# Sheet1.net
KiCad netlist of a schematic drawn in Altium Designer
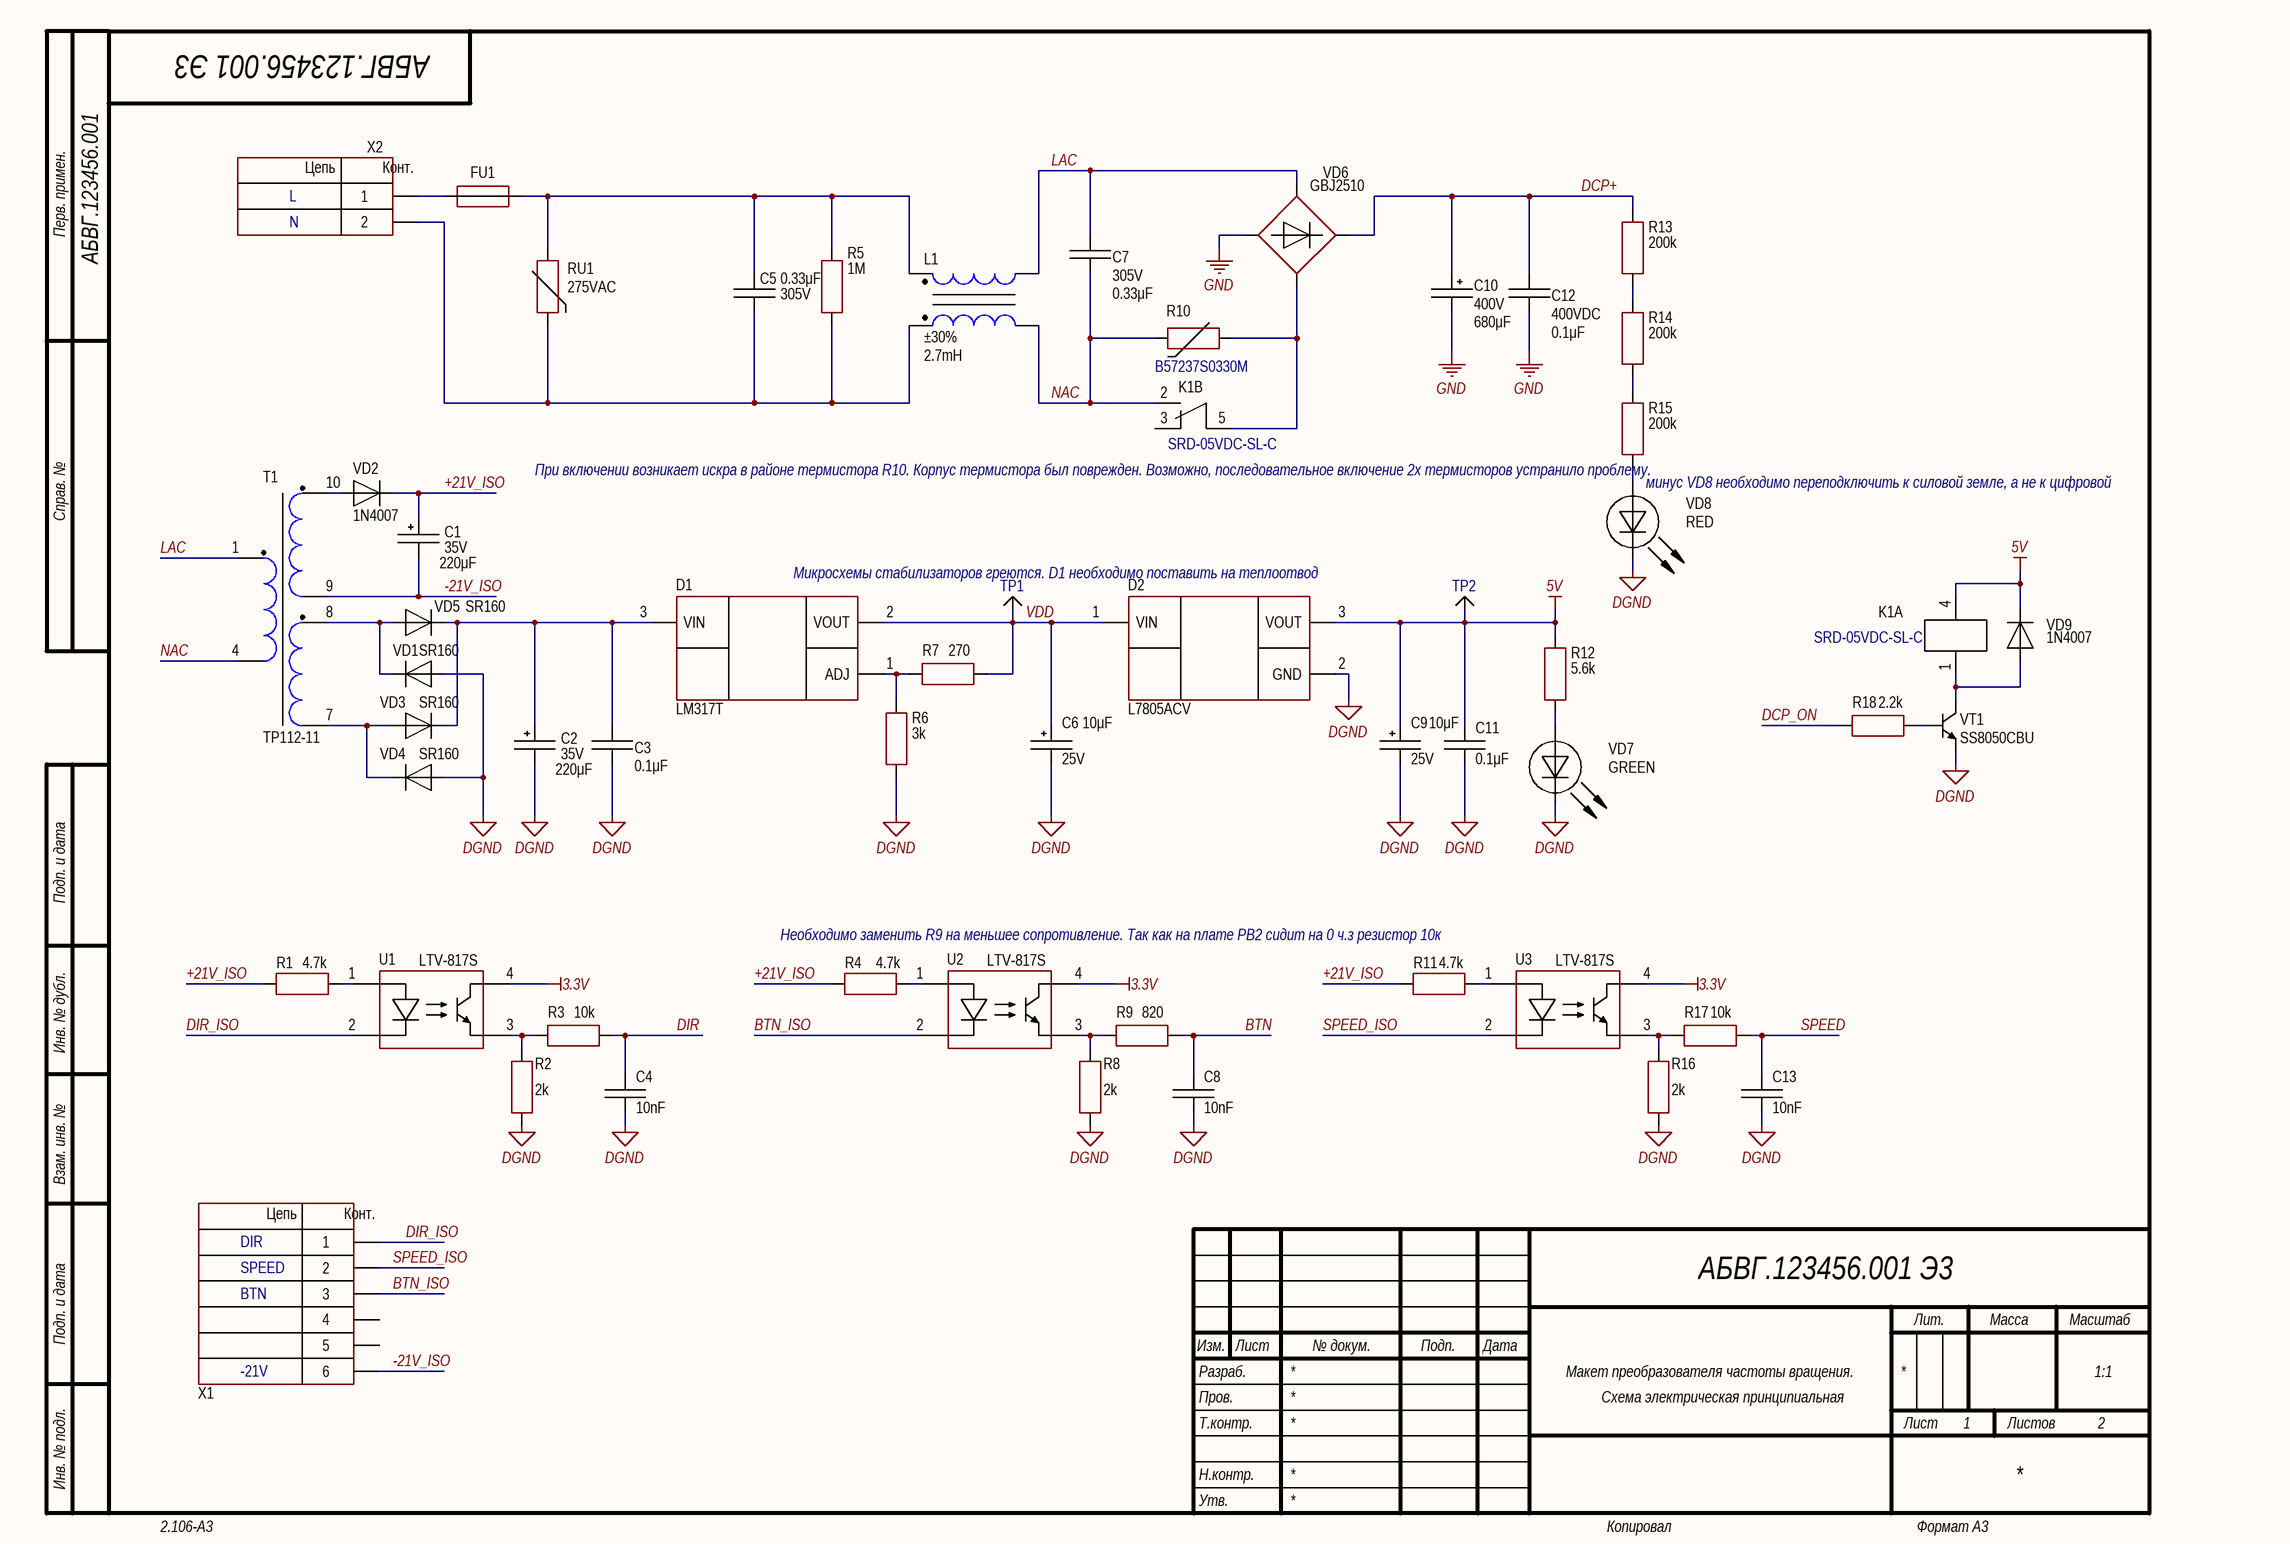
[diagram p0: Sheet1.SchDoc]

(export (version "E")
  (design (tool "Eeschema 10.0.6"))
  (components
    (comp (ref "C1")
      (value "220μF")
      (footprint "CAP: D8C3.5H12")
      (fields
        (field (name "MANUFACTURER") "?")
        (field (name "PARTNUMBER") "9000565901")
        (field (name "VALUEMANUFACTURERPARTNUMBER") "Aluminium capacitor, 220μF, 35V, ±20%, 54mOhm, 8x12x3.5 mm, -40...+105°C")
        (field (name "VOLTAGE") "35V")
      )
      (libsource (lib "capacitor") (part "Aluminium"))
    )
    (comp (ref "C2")
      (value "220μF")
      (footprint "CAP: D8C3.5H12")
      (fields
        (field (name "MANUFACTURER") "?")
        (field (name "PARTNUMBER") "9000565901")
        (field (name "VALUEMANUFACTURERPARTNUMBER") "Aluminium capacitor, 220μF, 35V, ±20%, 54mOhm, 8x12x3.5 mm, -40...+105°C")
        (field (name "VOLTAGE") "35V")
      )
      (libsource (lib "capacitor") (part "Aluminium"))
    )
    (comp (ref "C3")
      (value "0.1μF")
      (footprint "CAP: 1206")
      (fields
        (field (name "PARTNUMBER") "Ceramic capacitor, 0.1μF,   50V")
        (field (name "VALUEMANUFACTURERPARTNUMBER") "Ceramic capacitor, 0.1μF, X7R, ±10%, 50V, 1206, -55...+125°C")
        (field (name "TOLERANCE") "±10%")
      )
      (libsource (lib "capacitor") (part "Ceramic_1206"))
    )
    (comp (ref "C4")
      (value "10nF")
      (footprint "CAP: 1206")
      (fields
        (field (name "PARTNUMBER") "Ceramic capacitor, 10nF,   50V")
        (field (name "VALUEMANUFACTURERPARTNUMBER") "Ceramic capacitor, 10nF, X7R, ±10%, 50V, 1206, -55...+125°C")
        (field (name "TOLERANCE") "±10%")
      )
      (libsource (lib "capacitor") (part "Ceramic_1206"))
    )
    (comp (ref "C5")
      (value "0.33μF")
      (footprint "CAP: B32922")
      (fields
        (field (name "MANUFACTURER") "Epcos")
        (field (name "PARTNUMBER") "B32922-C3334-K")
        (field (name "VALUEMANUFACTURERPARTNUMBER") "Film capacitor X2, 0.33μF, 305V, ±10%, ?, 18x14x8, -40...+110°C")
        (field (name "VOLTAGE") "305V")
      )
      (libsource (lib "capacitor") (part "Film"))
    )
    (comp (ref "C6")
      (value "10μF")
      (footprint "CAP: D5C2H11")
      (fields
        (field (name "MANUFACTURER") "?")
        (field (name "PARTNUMBER") "9000565842")
        (field (name "VALUEMANUFACTURERPARTNUMBER") "Aluminium capacitor, 10μF, 25V, ±20%, 54mOhm, ?, -40...+105°C")
        (field (name "VOLTAGE") "25V")
      )
      (libsource (lib "capacitor") (part "Aluminium"))
    )
    (comp (ref "C7")
      (value "0.33μF")
      (footprint "CAP: B32922")
      (fields
        (field (name "MANUFACTURER") "Epcos")
        (field (name "PARTNUMBER") "B32922-C3334-K")
        (field (name "VALUEMANUFACTURERPARTNUMBER") "Film capacitor X2, 0.33μF, 305V, ±10%, ?, 18x14x8, -40...+110°C")
        (field (name "VOLTAGE") "305V")
      )
      (libsource (lib "capacitor") (part "Film"))
    )
    (comp (ref "C8")
      (value "10nF")
      (footprint "CAP: 1206")
      (fields
        (field (name "PARTNUMBER") "Ceramic capacitor, 10nF,   50V")
        (field (name "VALUEMANUFACTURERPARTNUMBER") "Ceramic capacitor, 10nF, X7R, ±10%, 50V, 1206, -55...+125°C")
        (field (name "TOLERANCE") "±10%")
      )
      (libsource (lib "capacitor") (part "Ceramic_1206"))
    )
    (comp (ref "C9")
      (value "10μF")
      (footprint "CAP: D5C2H11")
      (fields
        (field (name "MANUFACTURER") "?")
        (field (name "PARTNUMBER") "9000565842")
        (field (name "VALUEMANUFACTURERPARTNUMBER") "Aluminium capacitor, 10μF, 25V, ±20%, 54mOhm, ?, -40...+105°C")
        (field (name "VOLTAGE") "25V")
      )
      (libsource (lib "capacitor") (part "Aluminium"))
    )
    (comp (ref "C10")
      (value "680μF")
      (footprint "CAP: D30C10H37")
      (fields
        (field (name "MANUFACTURER") "JB Capacitors")
        (field (name "PARTNUMBER") "JNE2G681M10003000600")
        (field (name "VALUEMANUFACTURERPARTNUMBER") "Aluminium capacitor, 680μF, 400V, ±20%, ?, 30x10x60 mm, -25...+105°C")
        (field (name "VOLTAGE") "400V")
      )
      (libsource (lib "capacitor") (part "Aluminium"))
    )
    (comp (ref "C11")
      (value "0.1μF")
      (footprint "CAP: 1206")
      (fields
        (field (name "PARTNUMBER") "Ceramic capacitor, 0.1μF,   50V")
        (field (name "VALUEMANUFACTURERPARTNUMBER") "Ceramic capacitor, 0.1μF, X7R, ±10%, 50V, 1206, -55...+125°C")
        (field (name "TOLERANCE") "±10%")
      )
      (libsource (lib "capacitor") (part "Ceramic_1206"))
    )
    (comp (ref "C12")
      (value "0.1μF")
      (footprint "CAP: B32673")
      (fields
        (field (name "MANUFACTURER") "Epcos")
        (field (name "PARTNUMBER") "B32683A4104J000")
        (field (name "VALUEMANUFACTURERPARTNUMBER") "Film capacitor, 0.1μF, 400VDC, ±10%, ?, 26.5x16.5x8.5 mm, -55...+100°C")
        (field (name "VOLTAGE") "400VDC")
      )
      (libsource (lib "capacitor") (part "Film"))
    )
    (comp (ref "C13")
      (value "10nF")
      (footprint "CAP: 1206")
      (fields
        (field (name "PARTNUMBER") "Ceramic capacitor, 10nF,   50V")
        (field (name "VALUEMANUFACTURERPARTNUMBER") "Ceramic capacitor, 10nF, X7R, ±10%, 50V, 1206, -55...+125°C")
        (field (name "TOLERANCE") "±10%")
      )
      (libsource (lib "capacitor") (part "Ceramic_1206"))
    )
    (comp (ref "D1")
      (value "~")
      (footprint "TO-220F")
      (description "Adjustable voltage regulator")
      (fields
        (field (name "MANUFACTURER") "STMicroelectronics")
        (field (name "VALUEMANUFACTURERPARTNUMBER") "Adjustable voltage regulator, , , , 0...125°C, TO-220SG")
        (field (name "PARTNUMBER") "LM317T")
      )
      (libsource (lib "ic-power-supply") (part "LM317"))
    )
    (comp (ref "D2")
      (value "~")
      (footprint "TO-220F")
      (description "Linear voltage regulator")
      (fields
        (field (name "MANUFACTURER") "STMicroelectronics")
        (field (name "VALUEMANUFACTURERPARTNUMBER") "Linear voltage regulator, , , , *, *")
        (field (name "PARTNUMBER") "L7805ACV")
      )
      (libsource (lib "ic-power-supply") (part "78XX"))
    )
    (comp (ref "FU1")
      (value "~")
      (footprint "FUSE: FH-101")
      (fields
        (field (name "MANUFACTURER") "Dragon City Industries")
        (field (name "PARTNUMBER") "FH-101")
        (field (name "VALUEMANUFACTURERPARTNUMBER") "*,  FH-101, *")
      )
      (libsource (lib "resistor") (part "FUSE"))
    )
    (comp (ref "K1")
      (value "Relay, Non Latching, SPDT , 10A , (250VAC , 110VDC)")
      (footprint "SRD-05VDC-SL-C")
      (fields
        (field (name "MANUFACTURER") "Ningbo Songle Relay")
        (field (name "PARTNUMBER") "SRD-05VDC-SL-C")
      )
      (libsource (lib "") (part "SRD-05VDC-SL-C_1"))
    )
    (comp (ref "L1")
      (value "2.7mH")
      (footprint "IND: B82723A")
      (fields
        (field (name "MANUFACTURER") "TDK (TDK-Lambda)")
        (field (name "PARTNUMBER") "B82723A2402N1")
        (field (name "VALUEMANUFACTURERPARTNUMBER") "Fixed inductor, 2.7mH, ±30%, B82723A, CuNi18Zn20, ")
        (field (name "TOLERANCE") "±30%")
      )
      (libsource (lib "inductor") (part "B82723A"))
    )
    (comp (ref "R1")
      (value "4.7k")
      (footprint "RES: 1206")
      (fields
        (field (name "MANUFACTURER") "Yageo")
        (field (name "PARTNUMBER") "RC1206JR-07100RL")
        (field (name "VALUEMANUFACTURERPARTNUMBER") "Resistor film, 4.7k, ±5%, 1206, 0.25W, -55...+125°C")
      )
      (libsource (lib "") (part "Resistor_1206_2"))
    )
    (comp (ref "R2")
      (value "2k")
      (footprint "RES: 1206")
      (fields
        (field (name "MANUFACTURER") "Yageo")
        (field (name "PARTNUMBER") "RC1206JR-07100RL")
        (field (name "VALUEMANUFACTURERPARTNUMBER") "Resistor film, 2k, ±5%, 1206, 0.25W, -55...+125°C")
      )
      (libsource (lib "resistor") (part "Resistor_1206"))
    )
    (comp (ref "R3")
      (value "10k")
      (footprint "RES: 1206")
      (fields
        (field (name "MANUFACTURER") "Yageo")
        (field (name "PARTNUMBER") "RC1206JR-07100RL")
        (field (name "VALUEMANUFACTURERPARTNUMBER") "Resistor film, 10k, ±5%, 1206, 0.25W, -55...+125°C")
      )
      (libsource (lib "") (part "Resistor_1206_1"))
    )
    (comp (ref "R4")
      (value "4.7k")
      (footprint "RES: 1206")
      (fields
        (field (name "MANUFACTURER") "Yageo")
        (field (name "PARTNUMBER") "RC1206JR-07100RL")
        (field (name "VALUEMANUFACTURERPARTNUMBER") "Resistor film, 4.7k, ±5%, 1206, 0.25W, -55...+125°C")
      )
      (libsource (lib "") (part "Resistor_1206_2"))
    )
    (comp (ref "R5")
      (value "1M")
      (footprint "RES: Axial 15mm")
      (fields (field (name "TOLERANCE") "±5%"))
      (libsource (lib "resistor") (part "Resistor_Axial"))
    )
    (comp (ref "R6")
      (value "3k")
      (footprint "RES: 1206")
      (fields
        (field (name "MANUFACTURER") "Yageo")
        (field (name "PARTNUMBER") "RC1206JR-07100RL")
        (field (name "VALUEMANUFACTURERPARTNUMBER") "Resistor film, 3k, ±5%, 1206, 0.25W, -55...+125°C")
      )
      (libsource (lib "resistor") (part "Resistor_1206"))
    )
    (comp (ref "R7")
      (value "270")
      (footprint "RES: 1206")
      (fields
        (field (name "MANUFACTURER") "Yageo")
        (field (name "PARTNUMBER") "RC1206JR-07100RL")
        (field (name "VALUEMANUFACTURERPARTNUMBER") "Resistor film, 270, ±5%, 1206, 0.25W, -55...+125°C")
      )
      (libsource (lib "") (part "Resistor_1206_2"))
    )
    (comp (ref "R8")
      (value "2k")
      (footprint "RES: 1206")
      (fields
        (field (name "MANUFACTURER") "Yageo")
        (field (name "PARTNUMBER") "RC1206JR-07100RL")
        (field (name "VALUEMANUFACTURERPARTNUMBER") "Resistor film, 2k, ±5%, 1206, 0.25W, -55...+125°C")
      )
      (libsource (lib "resistor") (part "Resistor_1206"))
    )
    (comp (ref "R9")
      (value "820")
      (footprint "RES: 1206")
      (fields
        (field (name "MANUFACTURER") "Yageo")
        (field (name "PARTNUMBER") "RC1206JR-07100RL")
        (field (name "VALUEMANUFACTURERPARTNUMBER") "Resistor film, 820, ±5%, 1206, 0.25W, -55...+125°C")
      )
      (libsource (lib "") (part "Resistor_1206_1"))
    )
    (comp (ref "R10")
      (value "~")
      (footprint "RES: B57237 (NTC)")
      (description "Maximum permissible capacitance 900uF")
      (fields
        (field (name "MANUFACTURER") "Epcos")
        (field (name "PARTNUMBER") "B57237S0330M")
        (field (name "VALUEMANUFACTURERPARTNUMBER") "NTC resistor, 33, ±20%, pitch 7.5mm, 2.5A, -55...+170°C")
      )
      (libsource (lib "resistor") (part "NTC"))
    )
    (comp (ref "R11")
      (value "4.7k")
      (footprint "RES: 1206")
      (fields
        (field (name "MANUFACTURER") "Yageo")
        (field (name "PARTNUMBER") "RC1206JR-07100RL")
        (field (name "VALUEMANUFACTURERPARTNUMBER") "Resistor film, 4.7k, ±5%, 1206, 0.25W, -55...+125°C")
      )
      (libsource (lib "") (part "Resistor_1206_2"))
    )
    (comp (ref "R12")
      (value "5.6k")
      (footprint "RES: 1206")
      (fields
        (field (name "MANUFACTURER") "Yageo")
        (field (name "PARTNUMBER") "RC1206JR-07100RL")
        (field (name "VALUEMANUFACTURERPARTNUMBER") "Resistor film, 5.6k, ±5%, 1206, 0.25W, -55...+125°C")
      )
      (libsource (lib "resistor") (part "Resistor_1206"))
    )
    (comp (ref "R13")
      (value "200k")
      (footprint "RES: 1206")
      (fields
        (field (name "MANUFACTURER") "Yageo")
        (field (name "PARTNUMBER") "RC1206JR-07100RL")
        (field (name "VALUEMANUFACTURERPARTNUMBER") "Resistor film, 200k, ±5%, 1206, 0.25W, -55...+125°C")
      )
      (libsource (lib "resistor") (part "Resistor_1206"))
    )
    (comp (ref "R14")
      (value "200k")
      (footprint "RES: 1206")
      (fields
        (field (name "MANUFACTURER") "Yageo")
        (field (name "PARTNUMBER") "RC1206JR-07100RL")
        (field (name "VALUEMANUFACTURERPARTNUMBER") "Resistor film, 200k, ±5%, 1206, 0.25W, -55...+125°C")
      )
      (libsource (lib "resistor") (part "Resistor_1206"))
    )
    (comp (ref "R15")
      (value "200k")
      (footprint "RES: 1206")
      (fields
        (field (name "MANUFACTURER") "Yageo")
        (field (name "PARTNUMBER") "RC1206JR-07100RL")
        (field (name "VALUEMANUFACTURERPARTNUMBER") "Resistor film, 200k, ±5%, 1206, 0.25W, -55...+125°C")
      )
      (libsource (lib "resistor") (part "Resistor_1206"))
    )
    (comp (ref "R16")
      (value "2k")
      (footprint "RES: 1206")
      (fields
        (field (name "MANUFACTURER") "Yageo")
        (field (name "PARTNUMBER") "RC1206JR-07100RL")
        (field (name "VALUEMANUFACTURERPARTNUMBER") "Resistor film, 2k, ±5%, 1206, 0.25W, -55...+125°C")
      )
      (libsource (lib "resistor") (part "Resistor_1206"))
    )
    (comp (ref "R17")
      (value "10k")
      (footprint "RES: 1206")
      (fields
        (field (name "MANUFACTURER") "Yageo")
        (field (name "PARTNUMBER") "RC1206JR-07100RL")
        (field (name "VALUEMANUFACTURERPARTNUMBER") "Resistor film, 10k, ±5%, 1206, 0.25W, -55...+125°C")
      )
      (libsource (lib "") (part "Resistor_1206_1"))
    )
    (comp (ref "R18")
      (value "2.2k")
      (footprint "RES: 1206")
      (fields
        (field (name "MANUFACTURER") "Yageo")
        (field (name "PARTNUMBER") "RC1206JR-07100RL")
        (field (name "VALUEMANUFACTURERPARTNUMBER") "Resistor film, 2.2k, ±5%, 1206, 0.25W, -55...+125°C")
      )
      (libsource (lib "") (part "Resistor_1206_2"))
    )
    (comp (ref "RU1")
      (value "~")
      (footprint "VARISTOR: B72214")
      (fields
        (field (name "MANUFACTURER") "EPCOS")
        (field (name "PARTNUMBER") "B72214-S 271-K101")
        (field (name "VALUEMANUFACTURERPARTNUMBER") "Varistor, 275VAC, pitch 7mm,  -40…85°C")
        (field (name "MAXVOLTAGE") "275VAC")
      )
      (libsource (lib "resistor") (part "Varistor"))
    )
    (comp (ref "T1")
      (value "~")
      (footprint "TRANS: TP-112")
      (fields
        (field (name "MANUFACTURER") "?")
        (field (name "VALUEMANUFACTURERPARTNUMBER") "Transformer, TP112-11")
        (field (name "PARTNUMBER") "TP112-11")
        (field (name "PACKAGE") "TP112-11")
      )
      (libsource (lib "transformer") (part "TP-112"))
    )
    (comp (ref "TP1")
      (value "Test_Point")
      (footprint "TEST POINT KEYSTONE")
      (libsource (lib "other") (part "Test_Point"))
    )
    (comp (ref "TP2")
      (value "Test_Point")
      (footprint "TEST POINT KEYSTONE")
      (libsource (lib "other") (part "Test_Point"))
    )
    (comp (ref "U1")
      (value "~")
      (footprint "4-SMD")
      (description "Optoisolator")
      (fields
        (field (name "MANUFACTURER") "Lite-On")
        (field (name "VALUEMANUFACTURERPARTNUMBER") "IC optoisolator, 4µs/3µs, 5000Vrms, 35V, -40...+125°C, 4-SMD")
        (field (name "PARTNUMBER") "LTV-817S")
      )
      (libsource (lib "optoisolator") (part "LTV-817"))
    )
    (comp (ref "U2")
      (value "~")
      (footprint "4-SMD")
      (description "Optoisolator")
      (fields
        (field (name "MANUFACTURER") "Lite-On")
        (field (name "VALUEMANUFACTURERPARTNUMBER") "IC optoisolator, 4µs/3µs, 5000Vrms, 35V, -40...+125°C, 4-SMD")
        (field (name "PARTNUMBER") "LTV-817S")
      )
      (libsource (lib "optoisolator") (part "LTV-817"))
    )
    (comp (ref "U3")
      (value "~")
      (footprint "4-SMD")
      (description "Optoisolator")
      (fields
        (field (name "MANUFACTURER") "Lite-On")
        (field (name "VALUEMANUFACTURERPARTNUMBER") "IC optoisolator, 4µs/3µs, 5000Vrms, 35V, -40...+125°C, 4-SMD")
        (field (name "PARTNUMBER") "LTV-817S")
      )
      (libsource (lib "optoisolator") (part "LTV-817"))
    )
    (comp (ref "VD1")
      (value "~")
      (footprint "DIODE: DO41")
      (fields
        (field (name "MANUFACTURER") "China")
        (field (name "VALUEMANUFACTURERPARTNUMBER") "Single diode, 60V, 1A, 700mV, ?, DO-41,  -65…+150°C")
        (field (name "VOLTAGE") "60V")
        (field (name "PARTNUMBER") "SR160")
      )
      (libsource (lib "diode") (part "Diode_single"))
    )
    (comp (ref "VD2")
      (value "~")
      (footprint "DIODE: DO41")
      (fields
        (field (name "MANUFACTURER") "Diotec Semiconductor")
        (field (name "VALUEMANUFACTURERPARTNUMBER") "Single diode, 1000V, 1A, 1.1V, , DO-41, -65...+175 C")
        (field (name "VOLTAGE") "1000V")
        (field (name "PARTNUMBER") "1N4007")
      )
      (libsource (lib "diode") (part "Diode_single"))
    )
    (comp (ref "VD3")
      (value "~")
      (footprint "DIODE: DO41")
      (fields
        (field (name "MANUFACTURER") "China")
        (field (name "VALUEMANUFACTURERPARTNUMBER") "Single diode, 60V, 1A, 700mV, ?, DO-41,  -65…+150°C")
        (field (name "VOLTAGE") "60V")
        (field (name "PARTNUMBER") "SR160")
      )
      (libsource (lib "diode") (part "Diode_single"))
    )
    (comp (ref "VD4")
      (value "~")
      (footprint "DIODE: DO41")
      (fields
        (field (name "MANUFACTURER") "China")
        (field (name "VALUEMANUFACTURERPARTNUMBER") "Single diode, 60V, 1A, 700mV, ?, DO-41,  -65…+150°C")
        (field (name "VOLTAGE") "60V")
        (field (name "PARTNUMBER") "SR160")
      )
      (libsource (lib "diode") (part "Diode_single"))
    )
    (comp (ref "VD5")
      (value "~")
      (footprint "DIODE: DO41")
      (fields
        (field (name "MANUFACTURER") "China")
        (field (name "VALUEMANUFACTURERPARTNUMBER") "Single diode, 60V, 1A, 700mV, ?, DO-41,  -65…+150°C")
        (field (name "VOLTAGE") "60V")
        (field (name "PARTNUMBER") "SR160")
      )
      (libsource (lib "diode") (part "Diode_single"))
    )
    (comp (ref "VD6")
      (value "~")
      (footprint "DIODE: GBJ FLAT")
      (fields
        (field (name "MANUFACTURER") "DIODES INC.")
        (field (name "VALUEMANUFACTURERPARTNUMBER") "Single phase rectifier, 1000V, 25A, 1.05V, GBJ, -56...+150°C")
        (field (name "VOLTAGE") "1000V")
        (field (name "PARTNUMBER") "GBJ2510")
      )
      (libsource (lib "diode") (part "GBJ2510"))
    )
    (comp (ref "VD7")
      (value "~")
      (footprint "LED: 1206G")
      (fields
        (field (name "VALUEMANUFACTURERPARTNUMBER") "LED, Green, *, *, *, -55...+150°C")
        (field (name "PARTNUMBER") "Green Led")
        (field (name "COLOR") "GREEN")
      )
      (libsource (lib "diode") (part "LED_single"))
    )
    (comp (ref "VD8")
      (value "~")
      (footprint "LED: 1206R")
      (fields
        (field (name "VALUEMANUFACTURERPARTNUMBER") "LED, RED, *, *, *, -55...+150°C")
        (field (name "PARTNUMBER") "Red Led")
        (field (name "COLOR") "RED")
      )
      (libsource (lib "diode") (part "LED_single"))
    )
    (comp (ref "VD9")
      (value "~")
      (footprint "DIODE: DO41")
      (fields
        (field (name "MANUFACTURER") "Diotec Semiconductor")
        (field (name "VALUEMANUFACTURERPARTNUMBER") "Single diode, 1000V, 1A, 1.1V, , DO-41, -65...+175 C")
        (field (name "VOLTAGE") "1000V")
        (field (name "PARTNUMBER") "1N4007")
      )
      (libsource (lib "diode") (part "Diode_single"))
    )
    (comp (ref "VT1")
      (value "~")
      (footprint "TO-92 - formed leads")
      (fields
        (field (name "MANUFACTURER") "ON Semiconductor")
        (field (name "VALUEMANUFACTURERPARTNUMBER") "NPN transistor, 40V, 1.5A, 190MHz, 1W, 0.5Vmax, 120...200, TO-92, 150°C")
        (field (name "PARTNUMBER") "SS8050CBU")
      )
      (libsource (lib "transistor") (part "SS8050CBU"))
    )
    (comp (ref "X1")
      (value "~")
      (footprint "CON: PLS-6")
      (fields
        (field (name "MANUFACTURER") "Connfly")
        (field (name "VALUEMANUFACTURERPARTNUMBER") "Connector, 6pin, 2.54mm, 500VAC, 3A")
        (field (name "PARTNUMBER") "PLS-6")
      )
      (libsource (lib "connector") (part "PLS-6"))
    )
    (comp (ref "X2")
      (value "~")
      (footprint "DG128-7.5-02P")
      (fields
        (field (name "MANUFACTURER") "KLS electronic co ltd")
        (field (name "VALUEMANUFACTURERPARTNUMBER") "Connector, 2pin, 9.53mm, 300VAC, 16A")
        (field (name "PARTNUMBER") "KLS2-128-7.50-02P-4S")
      )
      (libsource (lib "connector") (part "KLS2-128-7.50-02P-4S (DG128-7.5-02P)"))
    )
  )
  (nets
    (net (code "1") (name "/+21V_ISO") (class "Default")
      (node (ref "C1") (pin "1") (pinfunction "1_1") (pintype "passive"))
      (node (ref "R1") (pin "1") (pinfunction "1_1") (pintype "passive"))
      (node (ref "R11") (pin "1") (pinfunction "1_1") (pintype "passive"))
      (node (ref "R4") (pin "1") (pinfunction "1_1") (pintype "passive"))
      (node (ref "VD2") (pin "2") (pinfunction "2_2") (pintype "passive"))
    )
    (net (code "2") (name "/-21V_ISO") (class "Default")
      (node (ref "C1") (pin "2") (pinfunction "2_2") (pintype "passive"))
      (node (ref "T1") (pin "9") (pinfunction "9_9") (pintype "power_in"))
      (node (ref "X1") (pin "6") (pinfunction "6_6") (pintype "power_in"))
    )
    (net (code "3") (name "/BTN") (class "Default")
      (node (ref "C8") (pin "2") (pinfunction "2_2") (pintype "passive"))
      (node (ref "R9") (pin "1") (pinfunction "1_1") (pintype "passive"))
    )
    (net (code "4") (name "/BTN_ISO") (class "Default")
      (node (ref "U2") (pin "2") (pinfunction "C_2") (pintype "passive"))
      (node (ref "X1") (pin "3") (pinfunction "3_3") (pintype "power_in"))
    )
    (net (code "5") (name "/DCP+") (class "Default")
      (node (ref "C10") (pin "1") (pinfunction "1_1") (pintype "passive"))
      (node (ref "C12") (pin "1") (pinfunction "1_1") (pintype "passive"))
      (node (ref "R13") (pin "2") (pinfunction "2_2") (pintype "passive"))
      (node (ref "VD6") (pin "3") (pinfunction "3_3") (pintype "passive"))
    )
    (net (code "6") (name "/DCP_ON") (class "Default")
      (node (ref "R18") (pin "1") (pinfunction "1_1") (pintype "passive"))
    )
    (net (code "7") (name "/DIR") (class "Default")
      (node (ref "C4") (pin "2") (pinfunction "2_2") (pintype "passive"))
      (node (ref "R3") (pin "1") (pinfunction "1_1") (pintype "passive"))
    )
    (net (code "8") (name "/DIR_ISO") (class "Default")
      (node (ref "U1") (pin "2") (pinfunction "C_2") (pintype "passive"))
      (node (ref "X1") (pin "1") (pinfunction "1_1") (pintype "passive"))
    )
    (net (code "9") (name "/LAC") (class "Default")
      (node (ref "C7") (pin "1") (pinfunction "1_1") (pintype "passive"))
      (node (ref "L1") (pin "1") (pinfunction "1_1") (pintype "passive"))
      (node (ref "T1") (pin "1") (pinfunction "1_1") (pintype "power_in"))
      (node (ref "VD6") (pin "2") (pinfunction "2_2") (pintype "passive"))
    )
    (net (code "10") (name "/NAC") (class "Default")
      (node (ref "C7") (pin "2") (pinfunction "2_2") (pintype "passive"))
      (node (ref "K1") (pin "2") (pinfunction "2_2") (pintype "passive"))
      (node (ref "L1") (pin "4") (pinfunction "4_4") (pintype "passive"))
      (node (ref "R10") (pin "2") (pinfunction "2_2") (pintype "passive"))
      (node (ref "T1") (pin "4") (pinfunction "4_4") (pintype "power_in"))
    )
    (net (code "11") (name "/SPEED") (class "Default")
      (node (ref "C13") (pin "2") (pinfunction "2_2") (pintype "passive"))
      (node (ref "R17") (pin "1") (pinfunction "1_1") (pintype "passive"))
    )
    (net (code "12") (name "/SPEED_ISO") (class "Default")
      (node (ref "U3") (pin "2") (pinfunction "C_2") (pintype "passive"))
      (node (ref "X1") (pin "2") (pinfunction "2_2") (pintype "passive"))
    )
    (net (code "13") (name "/VDD") (class "Default")
      (node (ref "C6") (pin "1") (pinfunction "1_1") (pintype "passive"))
      (node (ref "D1") (pin "2") (pinfunction "VOUT_2") (pintype "passive"))
      (node (ref "D2") (pin "1") (pinfunction "VIN_1") (pintype "passive"))
      (node (ref "R7") (pin "2") (pinfunction "2_2") (pintype "passive"))
      (node (ref "TP1") (pin "1") (pinfunction "1_1") (pintype "passive"))
    )
    (net (code "14") (name "3.3V") (class "Default")
      (node (ref "U1") (pin "4") (pinfunction "C_4") (pintype "passive"))
      (node (ref "U2") (pin "4") (pinfunction "C_4") (pintype "passive"))
      (node (ref "U3") (pin "4") (pinfunction "C_4") (pintype "passive"))
    )
    (net (code "15") (name "5V") (class "Default")
      (node (ref "C11") (pin "2") (pinfunction "2_2") (pintype "passive"))
      (node (ref "C9") (pin "1") (pinfunction "1_1") (pintype "passive"))
      (node (ref "D2") (pin "3") (pinfunction "VOUT_3") (pintype "passive"))
      (node (ref "K1") (pin "4") (pinfunction "4_4") (pintype "passive"))
      (node (ref "R12") (pin "2") (pinfunction "2_2") (pintype "passive"))
      (node (ref "TP2") (pin "1") (pinfunction "1_1") (pintype "passive"))
      (node (ref "VD9") (pin "2") (pinfunction "2_2") (pintype "passive"))
    )
    (net (code "16") (name "DGND") (class "Default")
      (node (ref "C11") (pin "1") (pinfunction "1_1") (pintype "passive"))
      (node (ref "C13") (pin "1") (pinfunction "1_1") (pintype "passive"))
      (node (ref "C2") (pin "2") (pinfunction "2_2") (pintype "passive"))
      (node (ref "C3") (pin "1") (pinfunction "1_1") (pintype "passive"))
      (node (ref "C4") (pin "1") (pinfunction "1_1") (pintype "passive"))
      (node (ref "C6") (pin "2") (pinfunction "2_2") (pintype "passive"))
      (node (ref "C8") (pin "1") (pinfunction "1_1") (pintype "passive"))
      (node (ref "C9") (pin "2") (pinfunction "2_2") (pintype "passive"))
      (node (ref "D2") (pin "2") (pinfunction "GND_2") (pintype "passive"))
      (node (ref "R16") (pin "1") (pinfunction "1_1") (pintype "passive"))
      (node (ref "R2") (pin "1") (pinfunction "1_1") (pintype "passive"))
      (node (ref "R6") (pin "1") (pinfunction "1_1") (pintype "passive"))
      (node (ref "R8") (pin "1") (pinfunction "1_1") (pintype "passive"))
      (node (ref "VD1") (pin "1") (pinfunction "1_1") (pintype "passive"))
      (node (ref "VD4") (pin "1") (pinfunction "1_1") (pintype "passive"))
      (node (ref "VD7") (pin "2") (pinfunction "C_2") (pintype "passive"))
      (node (ref "VD8") (pin "2") (pinfunction "C_2") (pintype "passive"))
      (node (ref "VT1") (pin "1") (pinfunction "E_1") (pintype "passive"))
    )
    (net (code "17") (name "GND") (class "Default")
      (node (ref "C10") (pin "2") (pinfunction "2_2") (pintype "passive"))
      (node (ref "C12") (pin "2") (pinfunction "2_2") (pintype "passive"))
      (node (ref "VD6") (pin "1") (pinfunction "1_1") (pintype "passive"))
    )
    (net (code "18") (name "Net-(C5-Pad1)") (class "Default")
      (node (ref "C5") (pin "1") (pinfunction "1_1") (pintype "passive"))
      (node (ref "FU1") (pin "2") (pinfunction "2_2") (pintype "passive"))
      (node (ref "L1") (pin "2") (pinfunction "2_2") (pintype "passive"))
      (node (ref "R5") (pin "2") (pinfunction "2_2") (pintype "passive"))
      (node (ref "RU1") (pin "1") (pinfunction "1_1") (pintype "passive"))
    )
    (net (code "19") (name "Net-(C5-Pad2)") (class "Default")
      (node (ref "C5") (pin "2") (pinfunction "2_2") (pintype "passive"))
      (node (ref "L1") (pin "3") (pinfunction "3_3") (pintype "passive"))
      (node (ref "R5") (pin "1") (pinfunction "1_1") (pintype "passive"))
      (node (ref "RU1") (pin "2") (pinfunction "2_2") (pintype "passive"))
      (node (ref "X2") (pin "2") (pinfunction "2_2") (pintype "passive"))
    )
    (net (code "20") (name "Net-(D1-ADJ)") (class "Default")
      (node (ref "D1") (pin "1") (pinfunction "ADJ_1") (pintype "passive"))
      (node (ref "R6") (pin "2") (pinfunction "2_2") (pintype "passive"))
      (node (ref "R7") (pin "1") (pinfunction "1_1") (pintype "passive"))
    )
    (net (code "21") (name "Net-(D1-VIN)") (class "Default")
      (node (ref "C2") (pin "1") (pinfunction "1_1") (pintype "passive"))
      (node (ref "C3") (pin "2") (pinfunction "2_2") (pintype "passive"))
      (node (ref "D1") (pin "3") (pinfunction "VIN_3") (pintype "passive"))
      (node (ref "VD3") (pin "2") (pinfunction "2_2") (pintype "passive"))
      (node (ref "VD5") (pin "2") (pinfunction "2_2") (pintype "passive"))
    )
    (net (code "22") (name "Net-(FU1-Pad1)") (class "Default")
      (node (ref "FU1") (pin "1") (pinfunction "1_1") (pintype "passive"))
      (node (ref "X2") (pin "1") (pinfunction "1_1") (pintype "passive"))
    )
    (net (code "23") (name "Net-(K1-Pad5)") (class "Default")
      (node (ref "K1") (pin "5") (pinfunction "5_5") (pintype "passive"))
      (node (ref "R10") (pin "1") (pinfunction "1_1") (pintype "passive"))
      (node (ref "VD6") (pin "4") (pinfunction "4_4") (pintype "passive"))
    )
    (net (code "24") (name "Net-(R13-Pad1)") (class "Default")
      (node (ref "R13") (pin "1") (pinfunction "1_1") (pintype "passive"))
      (node (ref "R14") (pin "2") (pinfunction "2_2") (pintype "passive"))
    )
    (net (code "25") (name "Net-(R14-Pad1)") (class "Default")
      (node (ref "R14") (pin "1") (pinfunction "1_1") (pintype "passive"))
      (node (ref "R15") (pin "2") (pinfunction "2_2") (pintype "passive"))
    )
    (net (code "26") (name "Net-(T1-Pad7)") (class "Default")
      (node (ref "T1") (pin "7") (pinfunction "7_7") (pintype "power_in"))
      (node (ref "VD3") (pin "1") (pinfunction "1_1") (pintype "passive"))
      (node (ref "VD4") (pin "2") (pinfunction "2_2") (pintype "passive"))
    )
    (net (code "27") (name "Net-(T1-Pad8)") (class "Default")
      (node (ref "T1") (pin "8") (pinfunction "8_8") (pintype "power_in"))
      (node (ref "VD1") (pin "2") (pinfunction "2_2") (pintype "passive"))
      (node (ref "VD5") (pin "1") (pinfunction "1_1") (pintype "passive"))
    )
    (net (code "28") (name "Net-(T1-Pad10)") (class "Default")
      (node (ref "T1") (pin "10") (pinfunction "10_10") (pintype "power_in"))
      (node (ref "VD2") (pin "1") (pinfunction "1_1") (pintype "passive"))
    )
    (net (code "29") (name "Net-(U1-A)") (class "Default")
      (node (ref "R1") (pin "2") (pinfunction "2_2") (pintype "passive"))
      (node (ref "U1") (pin "1") (pinfunction "A_1") (pintype "passive"))
    )
    (net (code "30") (name "Net-(U1-E)") (class "Default")
      (node (ref "R2") (pin "2") (pinfunction "2_2") (pintype "passive"))
      (node (ref "R3") (pin "2") (pinfunction "2_2") (pintype "passive"))
      (node (ref "U1") (pin "3") (pinfunction "E_3") (pintype "passive"))
    )
    (net (code "31") (name "Net-(U2-A)") (class "Default")
      (node (ref "R4") (pin "2") (pinfunction "2_2") (pintype "passive"))
      (node (ref "U2") (pin "1") (pinfunction "A_1") (pintype "passive"))
    )
    (net (code "32") (name "Net-(U2-E)") (class "Default")
      (node (ref "R8") (pin "2") (pinfunction "2_2") (pintype "passive"))
      (node (ref "R9") (pin "2") (pinfunction "2_2") (pintype "passive"))
      (node (ref "U2") (pin "3") (pinfunction "E_3") (pintype "passive"))
    )
    (net (code "33") (name "Net-(U3-A)") (class "Default")
      (node (ref "R11") (pin "2") (pinfunction "2_2") (pintype "passive"))
      (node (ref "U3") (pin "1") (pinfunction "A_1") (pintype "passive"))
    )
    (net (code "34") (name "Net-(U3-E)") (class "Default")
      (node (ref "R16") (pin "2") (pinfunction "2_2") (pintype "passive"))
      (node (ref "R17") (pin "2") (pinfunction "2_2") (pintype "passive"))
      (node (ref "U3") (pin "3") (pinfunction "E_3") (pintype "passive"))
    )
    (net (code "35") (name "Net-(VD7-A)") (class "Default")
      (node (ref "R12") (pin "1") (pinfunction "1_1") (pintype "passive"))
      (node (ref "VD7") (pin "1") (pinfunction "A_1") (pintype "passive"))
    )
    (net (code "36") (name "Net-(VD8-A)") (class "Default")
      (node (ref "R15") (pin "1") (pinfunction "1_1") (pintype "passive"))
      (node (ref "VD8") (pin "1") (pinfunction "A_1") (pintype "passive"))
    )
    (net (code "37") (name "Net-(VT1-B)") (class "Default")
      (node (ref "R18") (pin "2") (pinfunction "2_2") (pintype "passive"))
      (node (ref "VT1") (pin "2") (pinfunction "B_2") (pintype "passive"))
    )
    (net (code "38") (name "Net-(VT1-C)") (class "Default")
      (node (ref "K1") (pin "1") (pinfunction "1_1") (pintype "passive"))
      (node (ref "VD9") (pin "1") (pinfunction "1_1") (pintype "passive"))
      (node (ref "VT1") (pin "3") (pinfunction "C_3") (pintype "passive"))
    )
    (net (code "39") (name "unconnected-(K1-Pad3)") (class "Default")
      (node (ref "K1") (pin "3") (pinfunction "3_3") (pintype "passive"))
    )
    (net (code "40") (name "unconnected-(X1-Pad4)") (class "Default")
      (node (ref "X1") (pin "4") (pinfunction "4_4") (pintype "power_in"))
    )
    (net (code "41") (name "unconnected-(X1-Pad5)") (class "Default")
      (node (ref "X1") (pin "5") (pinfunction "5_5") (pintype "power_in"))
    )
  )
)
